# pid_driver.net
KiCad netlist of a schematic drawn in EAGLE
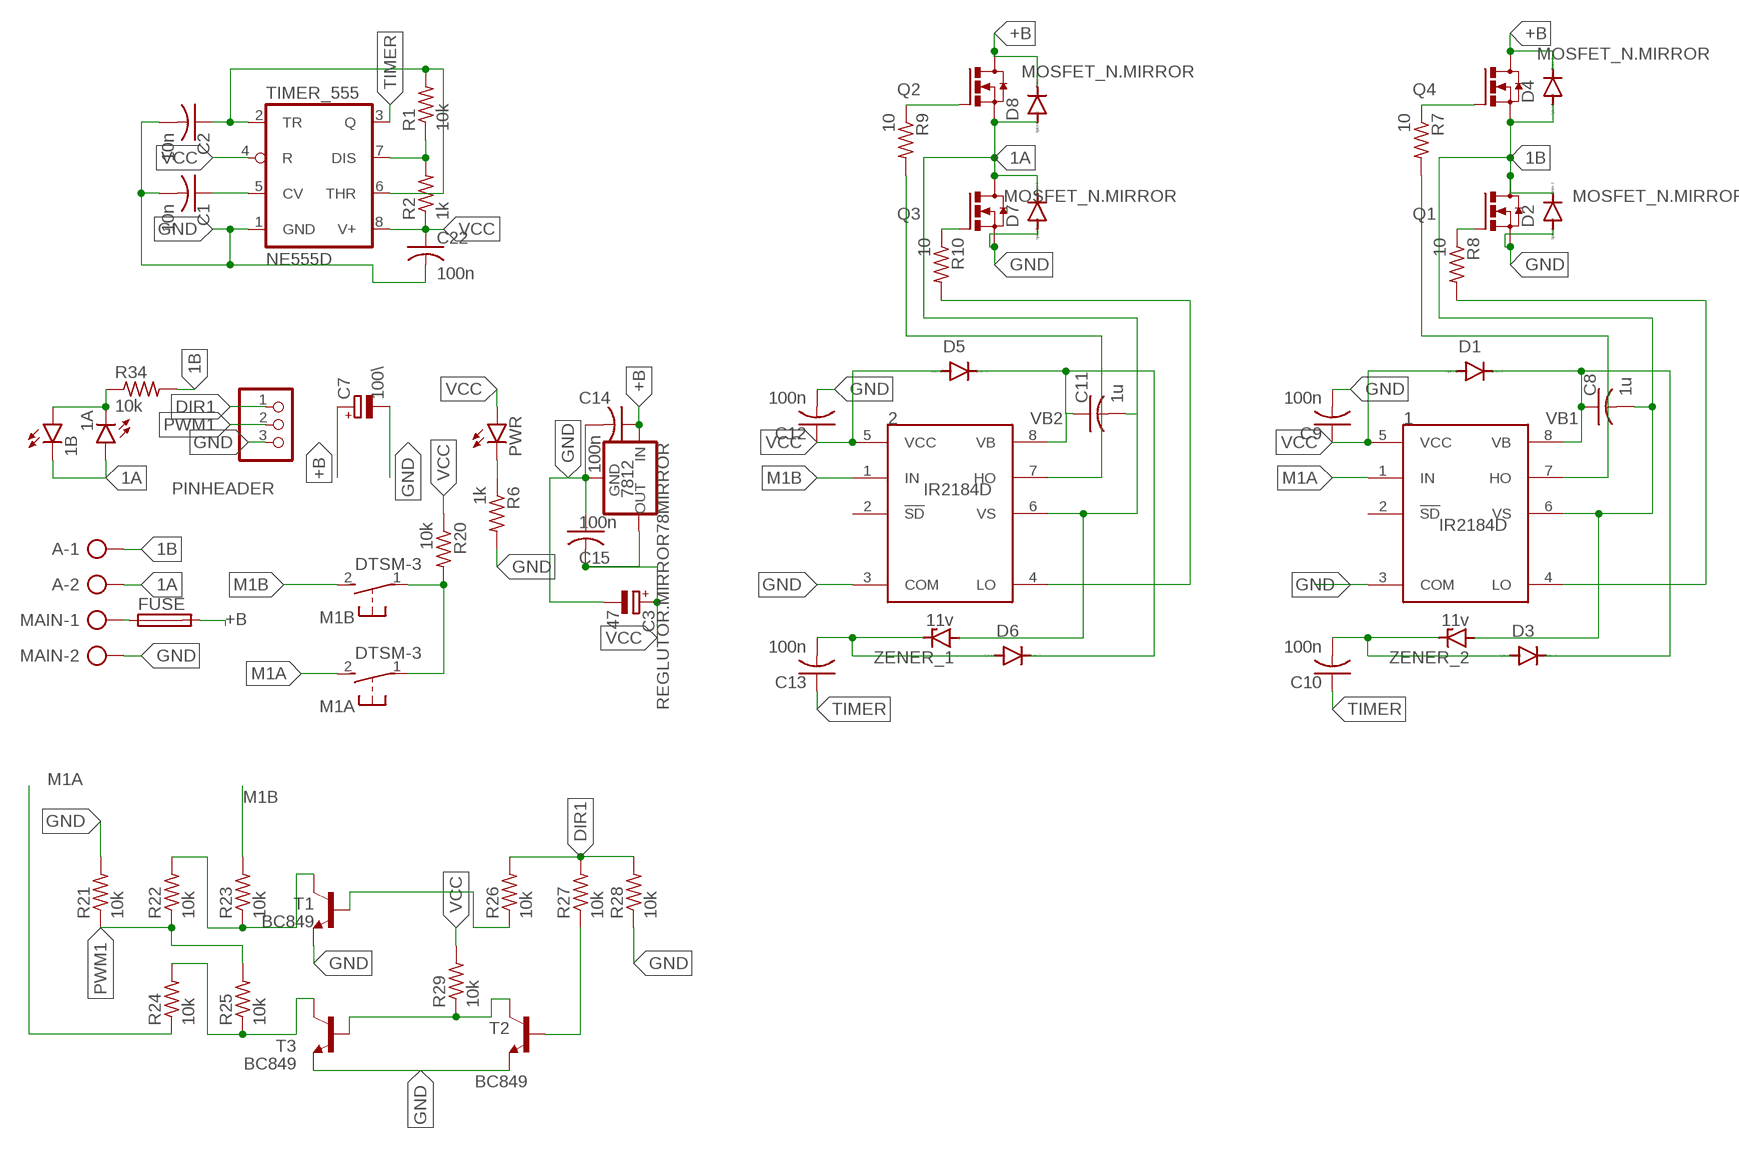
[diagram p0: schematic, sheet 1]

(export (version "E")
  (design (tool "Eeschema 10.0.6"))
  (components
    (comp (ref "1")
      (value "IR2184D")
      (footprint "eagle-import:DIL08")
      (libsource (lib "eagle-import") (part "IR2184D"))
    )
    (comp (ref "1A")
      (value "LEDCHIPLED_1206")
      (footprint "eagle-import:CHIPLED_1206")
      (libsource (lib "eagle-import") (part "LEDCHIPLED_1206"))
    )
    (comp (ref "1B")
      (value "LEDCHIPLED_1206")
      (footprint "eagle-import:CHIPLED_1206")
      (libsource (lib "eagle-import") (part "LEDCHIPLED_1206"))
    )
    (comp (ref "2")
      (value "IR2184D")
      (footprint "eagle-import:DIL08")
      (libsource (lib "eagle-import") (part "IR2184D"))
    )
    (comp (ref "7812")
      (value "REGLUTOR.MIRROR78MIRROR")
      (footprint "eagle-import:78MIRROR")
      (libsource (lib "eagle-import") (part "REGLUTOR.MIRROR78MIRROR"))
    )
    (comp (ref "A")
      (value "AK300/22")
      (footprint "eagle-import:XTALRR488W60L1090T465H350B")
      (libsource (lib "eagle-import") (part "AK300/22"))
    )
    (comp (ref "C1")
      (value "10n")
      (footprint "eagle-import:C1206K")
      (libsource (lib "eagle-import") (part "C-USC1206K"))
    )
    (comp (ref "C2")
      (value "10n")
      (footprint "eagle-import:C1206K")
      (libsource (lib "eagle-import") (part "C-USC1206K"))
    )
    (comp (ref "C3")
      (value "47")
      (footprint "eagle-import:E5-10,5")
      (libsource (lib "eagle-import") (part "CPOL-EUE5-10.5"))
    )
    (comp (ref "C7")
      (value "100\\")
      (footprint "eagle-import:E5-10,5")
      (libsource (lib "eagle-import") (part "CPOL-EUE5-10.5"))
    )
    (comp (ref "C8")
      (value "1u")
      (footprint "eagle-import:C1206K")
      (libsource (lib "eagle-import") (part "C-USC1206K"))
    )
    (comp (ref "C9")
      (value "100n")
      (footprint "eagle-import:C1206K")
      (libsource (lib "eagle-import") (part "C-USC1206K"))
    )
    (comp (ref "C10")
      (value "100n")
      (footprint "eagle-import:C1206K")
      (libsource (lib "eagle-import") (part "C-USC1206K"))
    )
    (comp (ref "C11")
      (value "1u")
      (footprint "eagle-import:C1206K")
      (libsource (lib "eagle-import") (part "C-USC1206K"))
    )
    (comp (ref "C12")
      (value "100n")
      (footprint "eagle-import:C1206K")
      (libsource (lib "eagle-import") (part "C-USC1206K"))
    )
    (comp (ref "C13")
      (value "100n")
      (footprint "eagle-import:C1206K")
      (libsource (lib "eagle-import") (part "C-USC1206K"))
    )
    (comp (ref "C14")
      (value "100n")
      (footprint "eagle-import:C1206K")
      (libsource (lib "eagle-import") (part "C-USC1206K"))
    )
    (comp (ref "C15")
      (value "100n")
      (footprint "eagle-import:C1206K")
      (libsource (lib "eagle-import") (part "C-USC1206K"))
    )
    (comp (ref "C22")
      (value "100n")
      (footprint "eagle-import:C1206K")
      (libsource (lib "eagle-import") (part "C-USC1206K"))
    )
    (comp (ref "D1")
      (value "DIODE-SMB")
      (footprint "eagle-import:SMB")
      (libsource (lib "eagle-import") (part "DIODE-SMB"))
    )
    (comp (ref "D2")
      (value "DIODE-SMB")
      (footprint "eagle-import:SMB")
      (libsource (lib "eagle-import") (part "DIODE-SMB"))
    )
    (comp (ref "D3")
      (value "DIODE-SMB")
      (footprint "eagle-import:SMB")
      (libsource (lib "eagle-import") (part "DIODE-SMB"))
    )
    (comp (ref "D4")
      (value "DIODE-SMB")
      (footprint "eagle-import:SMB")
      (libsource (lib "eagle-import") (part "DIODE-SMB"))
    )
    (comp (ref "D5")
      (value "DIODE-SMB")
      (footprint "eagle-import:SMB")
      (libsource (lib "eagle-import") (part "DIODE-SMB"))
    )
    (comp (ref "D6")
      (value "DIODE-SMB")
      (footprint "eagle-import:SMB")
      (libsource (lib "eagle-import") (part "DIODE-SMB"))
    )
    (comp (ref "D7")
      (value "DIODE-SMB")
      (footprint "eagle-import:SMB")
      (libsource (lib "eagle-import") (part "DIODE-SMB"))
    )
    (comp (ref "D8")
      (value "DIODE-SMB")
      (footprint "eagle-import:SMB")
      (libsource (lib "eagle-import") (part "DIODE-SMB"))
    )
    (comp (ref "FUSE")
      (value "FUSE_HOLDER")
      (footprint "eagle-import:SH22,5A")
      (libsource (lib "eagle-import") (part "FUSE_HOLDER"))
    )
    (comp (ref "M1A")
      (value "DTSM-3")
      (footprint "eagle-import:DTSM-3")
      (libsource (lib "eagle-import") (part "DTSM-3"))
    )
    (comp (ref "M1B")
      (value "DTSM-3")
      (footprint "eagle-import:DTSM-3")
      (libsource (lib "eagle-import") (part "DTSM-3"))
    )
    (comp (ref "MAIN")
      (value "AK300/22")
      (footprint "eagle-import:XTALRR488W60L1090T465H350B")
      (libsource (lib "eagle-import") (part "AK300/22"))
    )
    (comp (ref "PINHEADER")
      (value "PINHD-1X3")
      (footprint "eagle-import:1X03")
      (libsource (lib "eagle-import") (part "PINHD-1X3"))
    )
    (comp (ref "PWR")
      (value "LEDCHIPLED_1206")
      (footprint "eagle-import:CHIPLED_1206")
      (libsource (lib "eagle-import") (part "LEDCHIPLED_1206"))
    )
    (comp (ref "Q1")
      (value "MOSFET_N.MIRROR")
      (footprint "eagle-import:TO220.MIRROR")
      (libsource (lib "eagle-import") (part "MOSFET_N.MIRROR"))
    )
    (comp (ref "Q2")
      (value "MOSFET_N.MIRROR")
      (footprint "eagle-import:TO220.MIRROR")
      (libsource (lib "eagle-import") (part "MOSFET_N.MIRROR"))
    )
    (comp (ref "Q3")
      (value "MOSFET_N.MIRROR")
      (footprint "eagle-import:TO220.MIRROR")
      (libsource (lib "eagle-import") (part "MOSFET_N.MIRROR"))
    )
    (comp (ref "Q4")
      (value "MOSFET_N.MIRROR")
      (footprint "eagle-import:TO220.MIRROR")
      (libsource (lib "eagle-import") (part "MOSFET_N.MIRROR"))
    )
    (comp (ref "R1")
      (value "10k")
      (footprint "eagle-import:M1206")
      (libsource (lib "eagle-import") (part "R-US_M1206"))
    )
    (comp (ref "R2")
      (value "1k")
      (footprint "eagle-import:M1206")
      (libsource (lib "eagle-import") (part "R-US_M1206"))
    )
    (comp (ref "R6")
      (value "1k")
      (footprint "eagle-import:M1206")
      (libsource (lib "eagle-import") (part "R-US_M1206"))
    )
    (comp (ref "R7")
      (value "10")
      (footprint "eagle-import:M1206")
      (libsource (lib "eagle-import") (part "R-US_M1206"))
    )
    (comp (ref "R8")
      (value "10")
      (footprint "eagle-import:M1206")
      (libsource (lib "eagle-import") (part "R-US_M1206"))
    )
    (comp (ref "R9")
      (value "10")
      (footprint "eagle-import:M1206")
      (libsource (lib "eagle-import") (part "R-US_M1206"))
    )
    (comp (ref "R10")
      (value "10")
      (footprint "eagle-import:M1206")
      (libsource (lib "eagle-import") (part "R-US_M1206"))
    )
    (comp (ref "R20")
      (value "10k")
      (footprint "eagle-import:M1206")
      (libsource (lib "eagle-import") (part "R-US_M1206"))
    )
    (comp (ref "R21")
      (value "10k")
      (footprint "eagle-import:R1206")
      (libsource (lib "eagle-import") (part "R-US_R1206"))
    )
    (comp (ref "R22")
      (value "10k")
      (footprint "eagle-import:R1206")
      (libsource (lib "eagle-import") (part "R-US_R1206"))
    )
    (comp (ref "R23")
      (value "10k")
      (footprint "eagle-import:R1206")
      (libsource (lib "eagle-import") (part "R-US_R1206"))
    )
    (comp (ref "R24")
      (value "10k")
      (footprint "eagle-import:R1206")
      (libsource (lib "eagle-import") (part "R-US_R1206"))
    )
    (comp (ref "R25")
      (value "10k")
      (footprint "eagle-import:R1206")
      (libsource (lib "eagle-import") (part "R-US_R1206"))
    )
    (comp (ref "R26")
      (value "10k")
      (footprint "eagle-import:R1206")
      (libsource (lib "eagle-import") (part "R-US_R1206"))
    )
    (comp (ref "R27")
      (value "10k")
      (footprint "eagle-import:R1206")
      (libsource (lib "eagle-import") (part "R-US_R1206"))
    )
    (comp (ref "R28")
      (value "10k")
      (footprint "eagle-import:R1206")
      (libsource (lib "eagle-import") (part "R-US_R1206"))
    )
    (comp (ref "R29")
      (value "10k")
      (footprint "eagle-import:R1206")
      (libsource (lib "eagle-import") (part "R-US_R1206"))
    )
    (comp (ref "R34")
      (value "10k")
      (footprint "eagle-import:M1206")
      (libsource (lib "eagle-import") (part "R-US_M1206"))
    )
    (comp (ref "T1")
      (value "BC849")
      (footprint "eagle-import:SOT23")
      (libsource (lib "eagle-import") (part "BC849"))
    )
    (comp (ref "T2")
      (value "BC849")
      (footprint "eagle-import:SOT23")
      (libsource (lib "eagle-import") (part "BC849"))
    )
    (comp (ref "T3")
      (value "BC849")
      (footprint "eagle-import:SOT23")
      (libsource (lib "eagle-import") (part "BC849"))
    )
    (comp (ref "TIMER_555")
      (value "NE555D")
      (footprint "eagle-import:SO08")
      (libsource (lib "eagle-import") (part "555DNE"))
    )
    (comp (ref "ZENER_1")
      (value "11v")
      (footprint "eagle-import:SOD80C")
      (libsource (lib "eagle-import") (part "ZENER-DIODESOD80C"))
    )
    (comp (ref "ZENER_2")
      (value "11v")
      (footprint "eagle-import:SOD80C")
      (libsource (lib "eagle-import") (part "ZENER-DIODESOD80C"))
    )
  )
  (nets
    (net (code "1") (name "+B") (class "Default")
      (node (ref "7812") (pin "IN") (pinfunction "IN_IN") (pintype "input"))
      (node (ref "C14") (pin "1") (pinfunction "1_1") (pintype "passive"))
      (node (ref "C7") (pin "+") (pinfunction "+_+") (pintype "passive"))
      (node (ref "D4") (pin "C") (pinfunction "C_C") (pintype "passive"))
      (node (ref "D8") (pin "C") (pinfunction "C_C") (pintype "passive"))
      (node (ref "FUSE") (pin "2") (pinfunction "2_2") (pintype "passive"))
      (node (ref "Q2") (pin "D") (pinfunction "D_D") (pintype "passive"))
      (node (ref "Q4") (pin "D") (pinfunction "D_D") (pintype "passive"))
    )
    (net (code "2") (name "1A") (class "Default")
      (node (ref "1A") (pin "A") (pinfunction "A_A") (pintype "passive"))
      (node (ref "1B") (pin "C") (pinfunction "C_C") (pintype "passive"))
      (node (ref "2") (pin "6") (pinfunction "VS_6") (pintype "power_in"))
      (node (ref "A") (pin "2") (pinfunction "KL_2") (pintype "passive"))
      (node (ref "C11") (pin "2") (pinfunction "2_2") (pintype "passive"))
      (node (ref "D7") (pin "C") (pinfunction "C_C") (pintype "passive"))
      (node (ref "D8") (pin "A") (pinfunction "A_A") (pintype "passive"))
      (node (ref "Q2") (pin "S") (pinfunction "S_S") (pintype "passive"))
      (node (ref "Q3") (pin "D") (pinfunction "D_D") (pintype "passive"))
      (node (ref "ZENER_1") (pin "A") (pinfunction "A_A") (pintype "passive"))
    )
    (net (code "3") (name "1B") (class "Default")
      (node (ref "1") (pin "6") (pinfunction "VS_6") (pintype "power_in"))
      (node (ref "A") (pin "1") (pinfunction "KL_1") (pintype "passive"))
      (node (ref "C8") (pin "2") (pinfunction "2_2") (pintype "passive"))
      (node (ref "D2") (pin "C") (pinfunction "C_C") (pintype "passive"))
      (node (ref "D4") (pin "A") (pinfunction "A_A") (pintype "passive"))
      (node (ref "Q1") (pin "D") (pinfunction "D_D") (pintype "passive"))
      (node (ref "Q4") (pin "S") (pinfunction "S_S") (pintype "passive"))
      (node (ref "R34") (pin "2") (pinfunction "2_2") (pintype "passive"))
      (node (ref "ZENER_2") (pin "A") (pinfunction "A_A") (pintype "passive"))
    )
    (net (code "4") (name "DIR1") (class "Default")
      (node (ref "PINHEADER") (pin "1") (pinfunction "1_1") (pintype "passive"))
      (node (ref "R26") (pin "2") (pinfunction "2_2") (pintype "passive"))
      (node (ref "R27") (pin "2") (pinfunction "2_2") (pintype "passive"))
      (node (ref "R28") (pin "2") (pinfunction "2_2") (pintype "passive"))
    )
    (net (code "5") (name "GND") (class "Default")
      (node (ref "1") (pin "3") (pinfunction "COM_3") (pintype "power_in"))
      (node (ref "2") (pin "3") (pinfunction "COM_3") (pintype "power_in"))
      (node (ref "7812") (pin "GND") (pinfunction "GND_GND") (pintype "input"))
      (node (ref "C1") (pin "2") (pinfunction "2_2") (pintype "passive"))
      (node (ref "C12") (pin "2") (pinfunction "2_2") (pintype "passive"))
      (node (ref "C14") (pin "2") (pinfunction "2_2") (pintype "passive"))
      (node (ref "C15") (pin "1") (pinfunction "1_1") (pintype "passive"))
      (node (ref "C2") (pin "2") (pinfunction "2_2") (pintype "passive"))
      (node (ref "C22") (pin "2") (pinfunction "2_2") (pintype "passive"))
      (node (ref "C3") (pin "-") (pinfunction "-_-") (pintype "passive"))
      (node (ref "C7") (pin "-") (pinfunction "-_-") (pintype "passive"))
      (node (ref "C9") (pin "2") (pinfunction "2_2") (pintype "passive"))
      (node (ref "D2") (pin "A") (pinfunction "A_A") (pintype "passive"))
      (node (ref "D7") (pin "A") (pinfunction "A_A") (pintype "passive"))
      (node (ref "MAIN") (pin "2") (pinfunction "KL_2") (pintype "passive"))
      (node (ref "PINHEADER") (pin "3") (pinfunction "3_3") (pintype "passive"))
      (node (ref "Q1") (pin "S") (pinfunction "S_S") (pintype "passive"))
      (node (ref "Q3") (pin "S") (pinfunction "S_S") (pintype "passive"))
      (node (ref "R21") (pin "2") (pinfunction "2_2") (pintype "passive"))
      (node (ref "R28") (pin "1") (pinfunction "1_1") (pintype "passive"))
      (node (ref "R6") (pin "2") (pinfunction "2_2") (pintype "passive"))
      (node (ref "T1") (pin "2") (pinfunction "E_2") (pintype "passive"))
      (node (ref "T2") (pin "2") (pinfunction "E_2") (pintype "passive"))
      (node (ref "T3") (pin "2") (pinfunction "E_2") (pintype "passive"))
      (node (ref "TIMER_555") (pin "1") (pinfunction "GND_1") (pintype "power_in"))
    )
    (net (code "6") (name "M1A") (class "Default")
      (node (ref "1") (pin "1") (pinfunction "IN_1") (pintype "input"))
      (node (ref "M1A") (pin "2") (pinfunction "2_2") (pintype "passive"))
      (node (ref "R24") (pin "1") (pinfunction "1_1") (pintype "passive"))
    )
    (net (code "7") (name "M1B") (class "Default")
      (node (ref "2") (pin "1") (pinfunction "IN_1") (pintype "input"))
      (node (ref "M1B") (pin "2") (pinfunction "2_2") (pintype "passive"))
      (node (ref "R23") (pin "2") (pinfunction "2_2") (pintype "passive"))
    )
    (net (code "8") (name "Net-(1-HO)") (class "Default")
      (node (ref "1") (pin "7") (pinfunction "HO_7") (pintype "output"))
      (node (ref "R7") (pin "2") (pinfunction "2_2") (pintype "passive"))
    )
    (net (code "9") (name "Net-(1-LO)") (class "Default")
      (node (ref "1") (pin "4") (pinfunction "LO_4") (pintype "output"))
      (node (ref "R8") (pin "2") (pinfunction "2_2") (pintype "passive"))
    )
    (net (code "10") (name "Net-(1A-PadC)") (class "Default")
      (node (ref "1A") (pin "C") (pinfunction "C_C") (pintype "passive"))
      (node (ref "1B") (pin "A") (pinfunction "A_A") (pintype "passive"))
      (node (ref "R34") (pin "1") (pinfunction "1_1") (pintype "passive"))
    )
    (net (code "11") (name "Net-(2-HO)") (class "Default")
      (node (ref "2") (pin "7") (pinfunction "HO_7") (pintype "output"))
      (node (ref "R9") (pin "2") (pinfunction "2_2") (pintype "passive"))
    )
    (net (code "12") (name "Net-(2-LO)") (class "Default")
      (node (ref "2") (pin "4") (pinfunction "LO_4") (pintype "output"))
      (node (ref "R10") (pin "2") (pinfunction "2_2") (pintype "passive"))
    )
    (net (code "13") (name "Net-(C10-Pad2)") (class "Default")
      (node (ref "C10") (pin "2") (pinfunction "2_2") (pintype "passive"))
      (node (ref "D3") (pin "A") (pinfunction "A_A") (pintype "passive"))
      (node (ref "ZENER_2") (pin "C") (pinfunction "C_C") (pintype "passive"))
    )
    (net (code "14") (name "Net-(C13-Pad2)") (class "Default")
      (node (ref "C13") (pin "2") (pinfunction "2_2") (pintype "passive"))
      (node (ref "D6") (pin "A") (pinfunction "A_A") (pintype "passive"))
      (node (ref "ZENER_1") (pin "C") (pinfunction "C_C") (pintype "passive"))
    )
    (net (code "15") (name "Net-(M1A-Pad1)") (class "Default")
      (node (ref "M1A") (pin "1") (pinfunction "1_1") (pintype "passive"))
      (node (ref "M1B") (pin "1") (pinfunction "1_1") (pintype "passive"))
      (node (ref "R20") (pin "2") (pinfunction "2_2") (pintype "passive"))
    )
    (net (code "16") (name "Net-(MAINA-KL)") (class "Default")
      (node (ref "FUSE") (pin "1") (pinfunction "1_1") (pintype "passive"))
      (node (ref "MAIN") (pin "1") (pinfunction "KL_1") (pintype "passive"))
    )
    (net (code "17") (name "Net-(PWR-PadC)") (class "Default")
      (node (ref "PWR") (pin "C") (pinfunction "C_C") (pintype "passive"))
      (node (ref "R6") (pin "1") (pinfunction "1_1") (pintype "passive"))
    )
    (net (code "18") (name "Net-(Q1-PadG)") (class "Default")
      (node (ref "Q1") (pin "G") (pinfunction "G_G") (pintype "passive"))
      (node (ref "R8") (pin "1") (pinfunction "1_1") (pintype "passive"))
    )
    (net (code "19") (name "Net-(Q2-PadG)") (class "Default")
      (node (ref "Q2") (pin "G") (pinfunction "G_G") (pintype "passive"))
      (node (ref "R9") (pin "1") (pinfunction "1_1") (pintype "passive"))
    )
    (net (code "20") (name "Net-(Q3-PadG)") (class "Default")
      (node (ref "Q3") (pin "G") (pinfunction "G_G") (pintype "passive"))
      (node (ref "R10") (pin "1") (pinfunction "1_1") (pintype "passive"))
    )
    (net (code "21") (name "Net-(Q4-PadG)") (class "Default")
      (node (ref "Q4") (pin "G") (pinfunction "G_G") (pintype "passive"))
      (node (ref "R7") (pin "1") (pinfunction "1_1") (pintype "passive"))
    )
    (net (code "22") (name "Net-(T1-B)") (class "Default")
      (node (ref "R26") (pin "1") (pinfunction "1_1") (pintype "passive"))
      (node (ref "T1") (pin "1") (pinfunction "B_1") (pintype "passive"))
    )
    (net (code "23") (name "Net-(T1-C)") (class "Default")
      (node (ref "R22") (pin "2") (pinfunction "2_2") (pintype "passive"))
      (node (ref "R23") (pin "1") (pinfunction "1_1") (pintype "passive"))
      (node (ref "T1") (pin "3") (pinfunction "C_3") (pintype "passive"))
    )
    (net (code "24") (name "Net-(T2-B)") (class "Default")
      (node (ref "R27") (pin "1") (pinfunction "1_1") (pintype "passive"))
      (node (ref "T2") (pin "1") (pinfunction "B_1") (pintype "passive"))
    )
    (net (code "25") (name "Net-(T2-C)") (class "Default")
      (node (ref "R29") (pin "1") (pinfunction "1_1") (pintype "passive"))
      (node (ref "T2") (pin "3") (pinfunction "C_3") (pintype "passive"))
      (node (ref "T3") (pin "1") (pinfunction "B_1") (pintype "passive"))
    )
    (net (code "26") (name "Net-(T3-C)") (class "Default")
      (node (ref "R24") (pin "2") (pinfunction "2_2") (pintype "passive"))
      (node (ref "R25") (pin "1") (pinfunction "1_1") (pintype "passive"))
      (node (ref "T3") (pin "3") (pinfunction "C_3") (pintype "passive"))
    )
    (net (code "27") (name "Net-(TIMER_555-CV)") (class "Default")
      (node (ref "C1") (pin "1") (pinfunction "1_1") (pintype "passive"))
      (node (ref "TIMER_555") (pin "5") (pinfunction "CV_5") (pintype "input"))
    )
    (net (code "28") (name "Net-(TIMER_555-DIS)") (class "Default")
      (node (ref "R1") (pin "1") (pinfunction "1_1") (pintype "passive"))
      (node (ref "R2") (pin "2") (pinfunction "2_2") (pintype "passive"))
      (node (ref "TIMER_555") (pin "7") (pinfunction "DIS_7") (pintype "input"))
    )
    (net (code "29") (name "Net-(TIMER_555-THR)") (class "Default")
      (node (ref "C2") (pin "1") (pinfunction "1_1") (pintype "passive"))
      (node (ref "R1") (pin "2") (pinfunction "2_2") (pintype "passive"))
      (node (ref "TIMER_555") (pin "2") (pinfunction "TR_2") (pintype "input"))
      (node (ref "TIMER_555") (pin "6") (pinfunction "THR_6") (pintype "input"))
    )
    (net (code "30") (name "PWM1") (class "Default")
      (node (ref "PINHEADER") (pin "2") (pinfunction "2_2") (pintype "passive"))
      (node (ref "R21") (pin "1") (pinfunction "1_1") (pintype "passive"))
      (node (ref "R22") (pin "1") (pinfunction "1_1") (pintype "passive"))
      (node (ref "R25") (pin "2") (pinfunction "2_2") (pintype "passive"))
    )
    (net (code "31") (name "TIMER") (class "Default")
      (node (ref "C10") (pin "1") (pinfunction "1_1") (pintype "passive"))
      (node (ref "C13") (pin "1") (pinfunction "1_1") (pintype "passive"))
      (node (ref "TIMER_555") (pin "3") (pinfunction "Q_3") (pintype "output"))
    )
    (net (code "32") (name "VB1") (class "Default")
      (node (ref "1") (pin "8") (pinfunction "VB_8") (pintype "power_in"))
      (node (ref "C8") (pin "1") (pinfunction "1_1") (pintype "passive"))
      (node (ref "D1") (pin "C") (pinfunction "C_C") (pintype "passive"))
      (node (ref "D3") (pin "C") (pinfunction "C_C") (pintype "passive"))
    )
    (net (code "33") (name "VB2") (class "Default")
      (node (ref "2") (pin "8") (pinfunction "VB_8") (pintype "power_in"))
      (node (ref "C11") (pin "1") (pinfunction "1_1") (pintype "passive"))
      (node (ref "D5") (pin "C") (pinfunction "C_C") (pintype "passive"))
      (node (ref "D6") (pin "C") (pinfunction "C_C") (pintype "passive"))
    )
    (net (code "34") (name "VCC") (class "Default")
      (node (ref "1") (pin "5") (pinfunction "VCC_5") (pintype "power_in"))
      (node (ref "2") (pin "5") (pinfunction "VCC_5") (pintype "power_in"))
      (node (ref "7812") (pin "OUT") (pinfunction "OUT_OUT") (pintype "passive"))
      (node (ref "C12") (pin "1") (pinfunction "1_1") (pintype "passive"))
      (node (ref "C15") (pin "2") (pinfunction "2_2") (pintype "passive"))
      (node (ref "C22") (pin "1") (pinfunction "1_1") (pintype "passive"))
      (node (ref "C3") (pin "+") (pinfunction "+_+") (pintype "passive"))
      (node (ref "C9") (pin "1") (pinfunction "1_1") (pintype "passive"))
      (node (ref "D1") (pin "A") (pinfunction "A_A") (pintype "passive"))
      (node (ref "D5") (pin "A") (pinfunction "A_A") (pintype "passive"))
      (node (ref "PWR") (pin "A") (pinfunction "A_A") (pintype "passive"))
      (node (ref "R2") (pin "1") (pinfunction "1_1") (pintype "passive"))
      (node (ref "R20") (pin "1") (pinfunction "1_1") (pintype "passive"))
      (node (ref "R29") (pin "2") (pinfunction "2_2") (pintype "passive"))
      (node (ref "TIMER_555") (pin "4") (pinfunction "R_4") (pintype "input"))
      (node (ref "TIMER_555") (pin "8") (pinfunction "V+_8") (pintype "power_in"))
    )
    (net (code "35") (name "unconnected-(1-~{SD}-Pad2)") (class "Default")
      (node (ref "1") (pin "2") (pinfunction "~{SD}_2") (pintype "input"))
    )
    (net (code "36") (name "unconnected-(2-~{SD}-Pad2)") (class "Default")
      (node (ref "2") (pin "2") (pinfunction "~{SD}_2") (pintype "input"))
    )
  )
)
